# connectors.net
KiCad netlist of a schematic drawn in Altium Designer
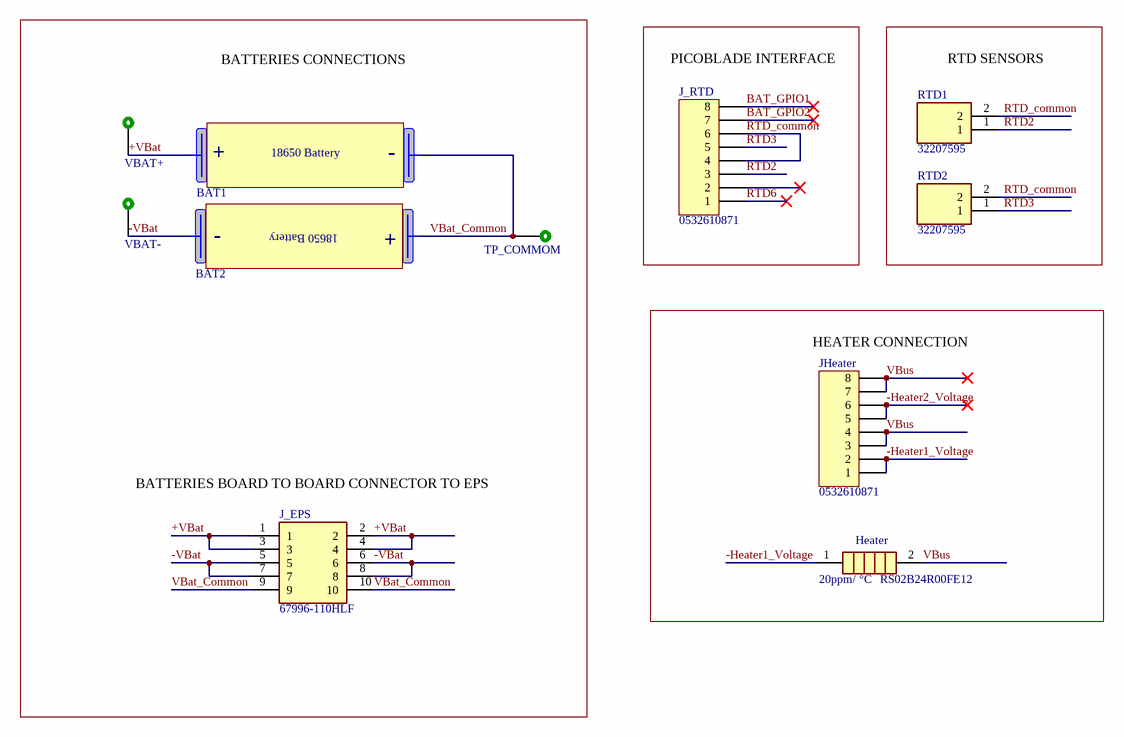
[diagram p0: connectors.SchDoc]

(export (version "E")
  (design (tool "Eeschema 10.0.6"))
  (components
    (comp (ref "BAT1")
      (value "18650 Battery contact strip slot")
      (footprint "BATTERY_18650_STRIP_CONTACT")
      (description "Slot using stip contact for 18650 batterie")
      (libsource (lib "schematics_library_legacy") (part "18650_Battery_contact_strip_slot"))
    )
    (comp (ref "BAT2")
      (value "18650 Battery contact strip slot")
      (footprint "BATTERY_18650_STRIP_CONTACT")
      (description "Slot using stip contact for 18650 batterie")
      (libsource (lib "") (part "18650_Battery_contact_strip_slot_1"))
    )
    (comp (ref "Heater")
      (value "RS02B24R00FE12")
      (footprint "RESAD3322W86L1422D475")
      (description "Wirewound Resistors - Through Hole 3watts 24ohms 1%")
      (fields (field (name "TEMPERATURE COEFFICIENT") "20ppm/ °C"))
      (libsource (lib "schematics_library_legacy") (part "RS02B24R00FE12"))
    )
    (comp (ref "JHeater")
      (value "0532610871")
      (footprint "PICOBLADE 8PIN RIGHT ANGLE")
      (description "PicoBlade 8 Position Right Angle Connector Header Surface Mount 0.049\" (1.25mm)")
      (fields
        (field (name "PARTNUMBER") "53261-0871")
        (field (name "MANUFACTURER") "Molex")
        (field (name "PUBLISHER") "Altium Limited")
      )
      (libsource (lib "schematics_library_legacy") (part "0532610871"))
    )
    (comp (ref "J_EPS")
      (value "67996-110HLF")
      (footprint "HDRV10W64P254_2X5_1270X502X521P")
      (description "Headers & Wire Housings 2X5P UNSHRD HDR 30 microinch gold")
      (fields (field (name "MOUSER PART NUMBER") "649-67996-110HLF"))
      (libsource (lib "schematics_library_legacy") (part "67996-110HLF"))
    )
    (comp (ref "J_RTD")
      (value "0532610871")
      (footprint "PICOBLADE 8PIN RIGHT ANGLE")
      (description "PicoBlade 8 Position Right Angle Connector Header Surface Mount 0.049\" (1.25mm)")
      (fields
        (field (name "PARTNUMBER") "53261-0871")
        (field (name "MANUFACTURER") "Molex")
        (field (name "PUBLISHER") "Altium Limited")
      )
      (libsource (lib "schematics_library_legacy") (part "0532610871"))
    )
    (comp (ref "RTD1")
      (value "32207595")
      (footprint "THRMC3216X70N")
      (description "1 kOhms RTD Platinum (Pt) ±0.3% 3850ppm/°C 1206 (3216 Metric)")
      (fields (field (name "MOUSER PART NUMBER") "956-32207595"))
      (libsource (lib "schematics_library_legacy") (part "32207595"))
    )
    (comp (ref "RTD2")
      (value "32207595")
      (footprint "THRMC3216X70N")
      (description "1 kOhms RTD Platinum (Pt) ±0.3% 3850ppm/°C 1206 (3216 Metric)")
      (fields (field (name "MOUSER PART NUMBER") "956-32207595"))
      (libsource (lib "schematics_library_legacy") (part "32207595"))
    )
    (comp (ref "TP_COMMOM")
      (value "TEST_POINT")
      (footprint "Test_Point")
      (description "Test Point")
      (libsource (lib "schematics_library_legacy") (part "TEST_POINT"))
    )
    (comp (ref "VBAT+")
      (value "TEST_POINT")
      (footprint "Test_Point")
      (description "Test Point")
      (libsource (lib "schematics_library_legacy") (part "TEST_POINT"))
    )
    (comp (ref "VBAT-")
      (value "TEST_POINT")
      (footprint "Test_Point")
      (description "Test Point")
      (libsource (lib "schematics_library_legacy") (part "TEST_POINT"))
    )
  )
  (nets
    (net (code "1") (name "/+VBat") (class "Default")
      (node (ref "BAT1") (pin "+") (pinfunction "Positive_+") (pintype "passive"))
      (node (ref "J_EPS") (pin "1") (pinfunction "1_1") (pintype "passive"))
      (node (ref "J_EPS") (pin "2") (pinfunction "2_2") (pintype "passive"))
      (node (ref "J_EPS") (pin "3") (pinfunction "3_3") (pintype "passive"))
      (node (ref "J_EPS") (pin "4") (pinfunction "4_4") (pintype "passive"))
      (node (ref "VBAT+") (pin "1") (pinfunction "1_1") (pintype "passive"))
    )
    (net (code "2") (name "/-Heater1_Voltage") (class "Default")
      (node (ref "Heater") (pin "1") (pinfunction "1_1") (pintype "passive"))
      (node (ref "JHeater") (pin "1") (pinfunction "1_1") (pintype "passive"))
      (node (ref "JHeater") (pin "2") (pinfunction "2_2") (pintype "passive"))
    )
    (net (code "3") (name "/-Heater2_Voltage") (class "Default")
      (node (ref "JHeater") (pin "5") (pinfunction "5_5") (pintype "passive"))
      (node (ref "JHeater") (pin "6") (pinfunction "6_6") (pintype "passive"))
    )
    (net (code "4") (name "/-VBat") (class "Default")
      (node (ref "BAT2") (pin "-") (pinfunction "Negative_-") (pintype "passive"))
      (node (ref "J_EPS") (pin "5") (pinfunction "5_5") (pintype "passive"))
      (node (ref "J_EPS") (pin "6") (pinfunction "6_6") (pintype "passive"))
      (node (ref "J_EPS") (pin "7") (pinfunction "7_7") (pintype "passive"))
      (node (ref "J_EPS") (pin "8") (pinfunction "8_8") (pintype "passive"))
      (node (ref "VBAT-") (pin "1") (pinfunction "1_1") (pintype "passive"))
    )
    (net (code "5") (name "/BAT_GPIO1") (class "Default")
      (node (ref "J_RTD") (pin "8") (pinfunction "8_8") (pintype "passive+no_connect"))
    )
    (net (code "6") (name "/BAT_GPIO2") (class "Default")
      (node (ref "J_RTD") (pin "7") (pinfunction "7_7") (pintype "passive+no_connect"))
    )
    (net (code "7") (name "/RTD2") (class "Default")
      (node (ref "J_RTD") (pin "3") (pinfunction "3_3") (pintype "passive"))
      (node (ref "RTD1") (pin "1") (pinfunction "1_1") (pintype "passive"))
    )
    (net (code "8") (name "/RTD3") (class "Default")
      (node (ref "J_RTD") (pin "5") (pinfunction "5_5") (pintype "passive"))
      (node (ref "RTD2") (pin "1") (pinfunction "1_1") (pintype "passive"))
    )
    (net (code "9") (name "/RTD6") (class "Default")
      (node (ref "J_RTD") (pin "1") (pinfunction "1_1") (pintype "passive+no_connect"))
    )
    (net (code "10") (name "/RTD_common") (class "Default")
      (node (ref "J_RTD") (pin "4") (pinfunction "4_4") (pintype "passive"))
      (node (ref "J_RTD") (pin "6") (pinfunction "6_6") (pintype "passive"))
      (node (ref "RTD1") (pin "2") (pinfunction "2_2") (pintype "passive"))
      (node (ref "RTD2") (pin "2") (pinfunction "2_2") (pintype "passive"))
    )
    (net (code "11") (name "/VBat_Common") (class "Default")
      (node (ref "BAT1") (pin "-") (pinfunction "Negative_-") (pintype "passive"))
      (node (ref "BAT2") (pin "+") (pinfunction "Positive_+") (pintype "passive"))
      (node (ref "J_EPS") (pin "10") (pinfunction "10_10") (pintype "passive"))
      (node (ref "J_EPS") (pin "9") (pinfunction "9_9") (pintype "passive"))
      (node (ref "TP_COMMOM") (pin "1") (pinfunction "1_1") (pintype "passive"))
    )
    (net (code "12") (name "/VBus") (class "Default")
      (node (ref "Heater") (pin "2") (pinfunction "2_2") (pintype "passive"))
      (node (ref "JHeater") (pin "3") (pinfunction "3_3") (pintype "passive"))
      (node (ref "JHeater") (pin "4") (pinfunction "4_4") (pintype "passive"))
      (node (ref "JHeater") (pin "7") (pinfunction "7_7") (pintype "passive"))
      (node (ref "JHeater") (pin "8") (pinfunction "8_8") (pintype "passive"))
    )
    (net (code "13") (name "unconnected-(J_RTD-Pad2)") (class "Default")
      (node (ref "J_RTD") (pin "2") (pinfunction "2_2") (pintype "passive+no_connect"))
    )
  )
)
